# EFR32_Port_Pins.net
KiCad netlist of a schematic drawn in Altium Designer
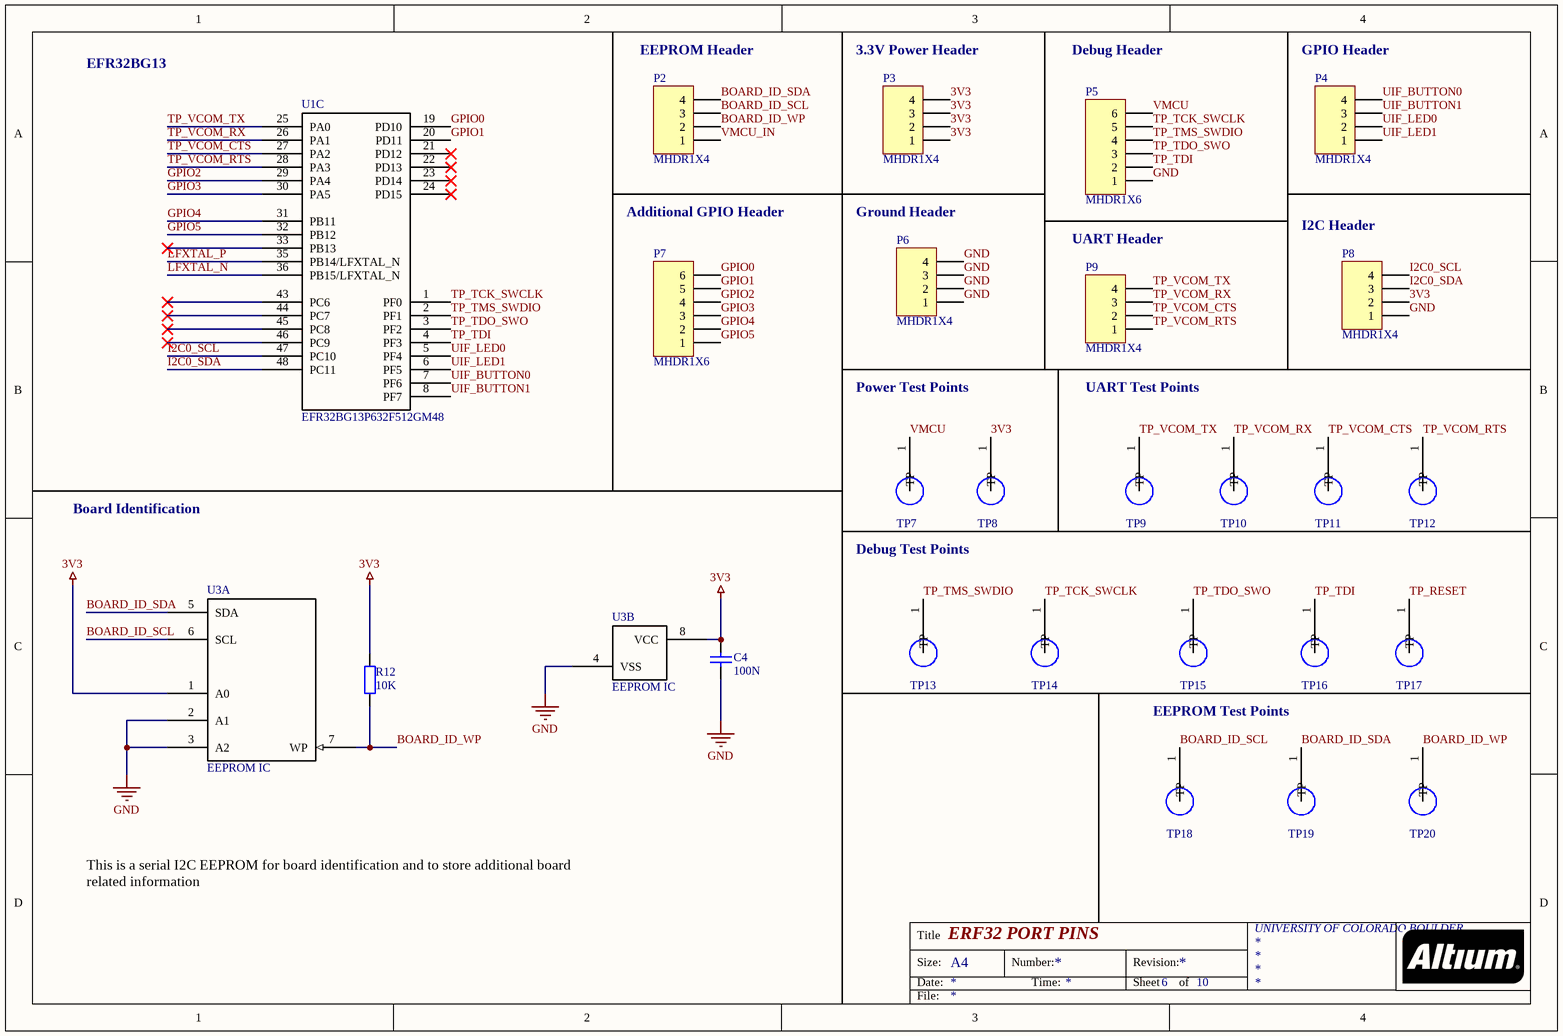
[diagram p0: EFR32_Port_Pins.SchDoc]

(export (version "E")
  (design (tool "Eeschema 10.0.6"))
  (components
    (comp (ref "C4")
      (value "100N")
      (footprint "1608[0603]")
      (description "CAP CER 0.1UF 16V X7R 0603")
      (fields
        (field (name "DIGI-KEY PART NUMBER") "1276-1005-1-ND")
        (field (name "MANUFACTURER") "Samsung Electro-Mechanics")
      )
      (libsource (lib "Miscellaneous Devices") (part "Cap"))
    )
    (comp (ref "P2")
      (value "MHDR1X4")
      (footprint "MHDR1X4")
      (description "CONN HEADER VERT 4POS 2.54MM")
      (fields
        (field (name "DIGI-KEY PART NUMBER") "732-5317-ND")
        (field (name "MANUFACTURER") "Würth Elektronik")
      )
      (libsource (lib "Miscellaneous Connectors") (part "MHDR1X4"))
    )
    (comp (ref "P3")
      (value "MHDR1X4")
      (footprint "MHDR1X4")
      (description "CONN HEADER VERT 4POS 2.54MM")
      (fields
        (field (name "DIGI-KEY PART NUMBER") "732-5317-ND")
        (field (name "MANUFACTURER") "Würth Elektronik")
      )
      (libsource (lib "Miscellaneous Connectors") (part "MHDR1X4"))
    )
    (comp (ref "P4")
      (value "MHDR1X4")
      (footprint "MHDR1X4")
      (description "CONN HEADER VERT 4POS 2.54MM")
      (fields
        (field (name "DIGI-KEY PART NUMBER") "732-5317-ND")
        (field (name "MANUFACTURER") "Würth Elektronik")
      )
      (libsource (lib "Miscellaneous Connectors") (part "MHDR1X4"))
    )
    (comp (ref "P5")
      (value "MHDR1X6")
      (footprint "MHDR1X6")
      (description "CONN HEADER VERT 6POS 2.54MM")
      (fields
        (field (name "DIGI-KEY PART NUMBER") "609-3263-ND")
        (field (name "MANUFACTURER") "Amphenol ICC (FCI)")
      )
      (libsource (lib "Miscellaneous Connectors") (part "MHDR1X6"))
    )
    (comp (ref "P6")
      (value "MHDR1X4")
      (footprint "MHDR1X4")
      (description "CONN HEADER VERT 4POS 2.54MM")
      (fields
        (field (name "DIGI-KEY PART NUMBER") "732-5317-ND")
        (field (name "MANUFACTURER") "Würth Elektronik")
      )
      (libsource (lib "Miscellaneous Connectors") (part "MHDR1X4"))
    )
    (comp (ref "P7")
      (value "MHDR1X6")
      (footprint "MHDR1X6")
      (description "CONN HEADER VERT 6POS 2.54MM")
      (fields
        (field (name "DIGI-KEY PART NUMBER") "609-3263-ND")
        (field (name "MANUFACTURER") "Amphenol ICC (FCI)")
      )
      (libsource (lib "Miscellaneous Connectors") (part "MHDR1X6"))
    )
    (comp (ref "P8")
      (value "MHDR1X4")
      (footprint "MHDR1X4")
      (description "CONN HEADER VERT 4POS 2.54MM")
      (fields
        (field (name "DIGI-KEY PART NUMBER") "732-5317-ND")
        (field (name "MANUFACTURER") "Würth Elektronik")
      )
      (libsource (lib "Miscellaneous Connectors") (part "MHDR1X4"))
    )
    (comp (ref "P9")
      (value "MHDR1X4")
      (footprint "MHDR1X4")
      (description "CONN HEADER VERT 4POS 2.54MM")
      (fields
        (field (name "DIGI-KEY PART NUMBER") "732-5317-ND")
        (field (name "MANUFACTURER") "Würth Elektronik")
      )
      (libsource (lib "Miscellaneous Connectors") (part "MHDR1X4"))
    )
    (comp (ref "R12")
      (value "10K")
      (footprint "AXIAL-0.4")
      (description "RES 10K OHM 1% 1/8W 0603")
      (fields
        (field (name "DIGI-KEY PART NUMBER") "RNCP0603FTD10K0CT-ND")
        (field (name "MANUFACTURER") "Stackpole Electronics Inc")
      )
      (libsource (lib "Miscellaneous Devices") (part "Res2"))
    )
    (comp (ref "TP7")
      (value "TP")
      (footprint "*TP380X203")
      (description "PC TEST POINT MINIATURE")
      (fields
        (field (name "MANUFACTURER") "Keystone Electronics")
        (field (name "DIGI-KEY PART NUMBER") "36-5019CT-ND")
      )
      (libsource (lib "TP") (part "TP"))
    )
    (comp (ref "TP8")
      (value "TP")
      (footprint "*TP380X203")
      (description "PC TEST POINT MINIATURE")
      (fields
        (field (name "MANUFACTURER") "Keystone Electronics")
        (field (name "DIGI-KEY PART NUMBER") "36-5019CT-ND")
      )
      (libsource (lib "TP") (part "TP"))
    )
    (comp (ref "TP9")
      (value "TP")
      (footprint "*TP380X203")
      (description "PC TEST POINT MINIATURE")
      (fields
        (field (name "MANUFACTURER") "Keystone Electronics")
        (field (name "DIGI-KEY PART NUMBER") "36-5019CT-ND")
      )
      (libsource (lib "TP") (part "TP"))
    )
    (comp (ref "TP10")
      (value "TP")
      (footprint "*TP380X203")
      (description "PC TEST POINT MINIATURE")
      (fields
        (field (name "MANUFACTURER") "Keystone Electronics")
        (field (name "DIGI-KEY PART NUMBER") "36-5019CT-ND")
      )
      (libsource (lib "TP") (part "TP"))
    )
    (comp (ref "TP11")
      (value "TP")
      (footprint "*TP380X203")
      (description "PC TEST POINT MINIATURE")
      (fields
        (field (name "MANUFACTURER") "Keystone Electronics")
        (field (name "DIGI-KEY PART NUMBER") "36-5019CT-ND")
      )
      (libsource (lib "TP") (part "TP"))
    )
    (comp (ref "TP12")
      (value "TP")
      (footprint "*TP380X203")
      (description "PC TEST POINT MINIATURE")
      (fields
        (field (name "MANUFACTURER") "Keystone Electronics")
        (field (name "DIGI-KEY PART NUMBER") "36-5019CT-ND")
      )
      (libsource (lib "TP") (part "TP"))
    )
    (comp (ref "TP13")
      (value "TP")
      (footprint "*TP380X203")
      (description "PC TEST POINT MINIATURE")
      (fields
        (field (name "MANUFACTURER") "Keystone Electronics")
        (field (name "DIGI-KEY PART NUMBER") "36-5019CT-ND")
      )
      (libsource (lib "TP") (part "TP"))
    )
    (comp (ref "TP14")
      (value "TP")
      (footprint "*TP380X203")
      (description "PC TEST POINT MINIATURE")
      (fields
        (field (name "MANUFACTURER") "Keystone Electronics")
        (field (name "DIGI-KEY PART NUMBER") "36-5019CT-ND")
      )
      (libsource (lib "TP") (part "TP"))
    )
    (comp (ref "TP15")
      (value "TP")
      (footprint "*TP380X203")
      (description "PC TEST POINT MINIATURE")
      (fields
        (field (name "MANUFACTURER") "Keystone Electronics")
        (field (name "DIGI-KEY PART NUMBER") "36-5019CT-ND")
      )
      (libsource (lib "TP") (part "TP"))
    )
    (comp (ref "TP16")
      (value "TP")
      (footprint "*TP380X203")
      (description "PC TEST POINT MINIATURE")
      (fields
        (field (name "MANUFACTURER") "Keystone Electronics")
        (field (name "DIGI-KEY PART NUMBER") "36-5019CT-ND")
      )
      (libsource (lib "TP") (part "TP"))
    )
    (comp (ref "TP17")
      (value "TP")
      (footprint "*TP380X203")
      (description "PC TEST POINT MINIATURE")
      (fields
        (field (name "MANUFACTURER") "Keystone Electronics")
        (field (name "DIGI-KEY PART NUMBER") "36-5019CT-ND")
      )
      (libsource (lib "TP") (part "TP"))
    )
    (comp (ref "TP18")
      (value "TP")
      (footprint "*TP380X203")
      (description "PC TEST POINT MINIATURE")
      (fields
        (field (name "MANUFACTURER") "Keystone Electronics")
        (field (name "DIGI-KEY PART NUMBER") "36-5019CT-ND")
      )
      (libsource (lib "TP") (part "TP"))
    )
    (comp (ref "TP19")
      (value "TP")
      (footprint "*TP380X203")
      (description "PC TEST POINT MINIATURE")
      (fields
        (field (name "MANUFACTURER") "Keystone Electronics")
        (field (name "DIGI-KEY PART NUMBER") "36-5019CT-ND")
      )
      (libsource (lib "TP") (part "TP"))
    )
    (comp (ref "TP20")
      (value "TP")
      (footprint "*TP380X203")
      (description "PC TEST POINT MINIATURE")
      (fields
        (field (name "MANUFACTURER") "Keystone Electronics")
        (field (name "DIGI-KEY PART NUMBER") "36-5019CT-ND")
      )
      (libsource (lib "TP") (part "TP"))
    )
    (comp (ref "U1")
      (value "EFR32BG13P632F512GM48")
      (footprint "*QFN50P700X700X90-49N")
      (description "MCU")
      (fields
        (field (name "MANUFACTURER") "Silicon Labs")
        (field (name "MANUFACTURER PART NUMBER") "EFR32BG13P632F512GM48-BR")
      )
      (libsource (lib "EFR32BG13") (part "EFR32BG13"))
    )
    (comp (ref "U3")
      (value "EEPROM IC")
      (footprint "*SON50P200X300X80-8N")
      (description "EEPROM 2K 256X8 SER EE 1.8V 18 I/O 10-BIT ADC")
      (fields
        (field (name "MOUSER PART NUMBER") "579-24AA024T-I/MNY")
        (field (name "MANUFACTURER PART NUMBER") "24AA024T-I/MNY")
      )
      (libsource (lib "EEPROM_IC") (part "EEPROM IC"))
    )
  )
  (nets
    (net (code "1") (name "/BOARD_ID_SCL") (class "Default")
      (node (ref "P2") (pin "3") (pinfunction "3_3") (pintype "passive"))
      (node (ref "TP18") (pin "1") (pinfunction "TP_1") (pintype "passive"))
      (node (ref "U3") (pin "6") (pinfunction "SCL_6") (pintype "passive"))
    )
    (net (code "2") (name "/BOARD_ID_SDA") (class "Default")
      (node (ref "P2") (pin "4") (pinfunction "4_4") (pintype "passive"))
      (node (ref "TP19") (pin "1") (pinfunction "TP_1") (pintype "passive"))
      (node (ref "U3") (pin "5") (pinfunction "SDA_5") (pintype "passive"))
    )
    (net (code "3") (name "/BOARD_ID_WP") (class "Default")
      (node (ref "P2") (pin "2") (pinfunction "2_2") (pintype "passive"))
      (node (ref "R12") (pin "1") (pinfunction "1_1") (pintype "passive"))
      (node (ref "TP20") (pin "1") (pinfunction "TP_1") (pintype "passive"))
      (node (ref "U3") (pin "7") (pinfunction "WP_7") (pintype "input"))
    )
    (net (code "4") (name "/GPIO0") (class "Default")
      (node (ref "P7") (pin "6") (pinfunction "6_6") (pintype "passive"))
      (node (ref "U1") (pin "19") (pinfunction "PD10_19") (pintype "passive"))
    )
    (net (code "5") (name "/GPIO1") (class "Default")
      (node (ref "P7") (pin "5") (pinfunction "5_5") (pintype "passive"))
      (node (ref "U1") (pin "20") (pinfunction "PD11_20") (pintype "passive"))
    )
    (net (code "6") (name "/GPIO2") (class "Default")
      (node (ref "P7") (pin "4") (pinfunction "4_4") (pintype "passive"))
      (node (ref "U1") (pin "29") (pinfunction "PA4_29") (pintype "passive"))
    )
    (net (code "7") (name "/GPIO3") (class "Default")
      (node (ref "P7") (pin "3") (pinfunction "3_3") (pintype "passive"))
      (node (ref "U1") (pin "30") (pinfunction "PA5_30") (pintype "passive"))
    )
    (net (code "8") (name "/GPIO4") (class "Default")
      (node (ref "P7") (pin "2") (pinfunction "2_2") (pintype "passive"))
      (node (ref "U1") (pin "31") (pinfunction "PB11_31") (pintype "passive"))
    )
    (net (code "9") (name "/GPIO5") (class "Default")
      (node (ref "P7") (pin "1") (pinfunction "1_1") (pintype "passive"))
      (node (ref "U1") (pin "32") (pinfunction "PB12_32") (pintype "passive"))
    )
    (net (code "10") (name "/I2C0_SCL") (class "Default")
      (node (ref "P8") (pin "4") (pinfunction "4_4") (pintype "passive"))
      (node (ref "U1") (pin "47") (pinfunction "PC10_47") (pintype "passive"))
    )
    (net (code "11") (name "/I2C0_SDA") (class "Default")
      (node (ref "P8") (pin "3") (pinfunction "3_3") (pintype "passive"))
      (node (ref "U1") (pin "48") (pinfunction "PC11_48") (pintype "passive"))
    )
    (net (code "12") (name "/LFXTAL_N") (class "Default")
      (node (ref "U1") (pin "36") (pinfunction "PB15/LFXTAL_N_36") (pintype "passive"))
    )
    (net (code "13") (name "/LFXTAL_P") (class "Default")
      (node (ref "U1") (pin "35") (pinfunction "PB14/LFXTAL_N_35") (pintype "passive"))
    )
    (net (code "14") (name "/TP_RESET") (class "Default")
      (node (ref "TP17") (pin "1") (pinfunction "TP_1") (pintype "passive"))
    )
    (net (code "15") (name "/TP_TCK_SWCLK") (class "Default")
      (node (ref "P5") (pin "5") (pinfunction "5_5") (pintype "passive"))
      (node (ref "TP14") (pin "1") (pinfunction "TP_1") (pintype "passive"))
      (node (ref "U1") (pin "1") (pinfunction "PF0_1") (pintype "passive"))
    )
    (net (code "16") (name "/TP_TDI") (class "Default")
      (node (ref "P5") (pin "2") (pinfunction "2_2") (pintype "passive"))
      (node (ref "TP16") (pin "1") (pinfunction "TP_1") (pintype "passive"))
      (node (ref "U1") (pin "4") (pinfunction "PF3_4") (pintype "passive"))
    )
    (net (code "17") (name "/TP_TDO_SWO") (class "Default")
      (node (ref "P5") (pin "3") (pinfunction "3_3") (pintype "passive"))
      (node (ref "TP15") (pin "1") (pinfunction "TP_1") (pintype "passive"))
      (node (ref "U1") (pin "3") (pinfunction "PF2_3") (pintype "passive"))
    )
    (net (code "18") (name "/TP_TMS_SWDIO") (class "Default")
      (node (ref "P5") (pin "4") (pinfunction "4_4") (pintype "passive"))
      (node (ref "TP13") (pin "1") (pinfunction "TP_1") (pintype "passive"))
      (node (ref "U1") (pin "2") (pinfunction "PF1_2") (pintype "passive"))
    )
    (net (code "19") (name "/TP_VCOM_CTS") (class "Default")
      (node (ref "P9") (pin "2") (pinfunction "2_2") (pintype "passive"))
      (node (ref "TP11") (pin "1") (pinfunction "TP_1") (pintype "passive"))
      (node (ref "U1") (pin "27") (pinfunction "PA2_27") (pintype "passive"))
    )
    (net (code "20") (name "/TP_VCOM_RTS") (class "Default")
      (node (ref "P9") (pin "1") (pinfunction "1_1") (pintype "passive"))
      (node (ref "TP12") (pin "1") (pinfunction "TP_1") (pintype "passive"))
      (node (ref "U1") (pin "28") (pinfunction "PA3_28") (pintype "passive"))
    )
    (net (code "21") (name "/TP_VCOM_RX") (class "Default")
      (node (ref "P9") (pin "3") (pinfunction "3_3") (pintype "passive"))
      (node (ref "TP10") (pin "1") (pinfunction "TP_1") (pintype "passive"))
      (node (ref "U1") (pin "26") (pinfunction "PA1_26") (pintype "passive"))
    )
    (net (code "22") (name "/TP_VCOM_TX") (class "Default")
      (node (ref "P9") (pin "4") (pinfunction "4_4") (pintype "passive"))
      (node (ref "TP9") (pin "1") (pinfunction "TP_1") (pintype "passive"))
      (node (ref "U1") (pin "25") (pinfunction "PA0_25") (pintype "passive"))
    )
    (net (code "23") (name "/UIF_BUTTON0") (class "Default")
      (node (ref "P4") (pin "4") (pinfunction "4_4") (pintype "passive"))
      (node (ref "U1") (pin "7") (pinfunction "PF6_7") (pintype "passive"))
    )
    (net (code "24") (name "/UIF_BUTTON1") (class "Default")
      (node (ref "P4") (pin "3") (pinfunction "3_3") (pintype "passive"))
      (node (ref "U1") (pin "8") (pinfunction "PF7_8") (pintype "passive"))
    )
    (net (code "25") (name "/UIF_LED0") (class "Default")
      (node (ref "P4") (pin "2") (pinfunction "2_2") (pintype "passive"))
      (node (ref "U1") (pin "5") (pinfunction "PF4_5") (pintype "passive"))
    )
    (net (code "26") (name "/UIF_LED1") (class "Default")
      (node (ref "P4") (pin "1") (pinfunction "1_1") (pintype "passive"))
      (node (ref "U1") (pin "6") (pinfunction "PF5_6") (pintype "passive"))
    )
    (net (code "27") (name "/VMCU") (class "Default")
      (node (ref "P5") (pin "6") (pinfunction "6_6") (pintype "passive"))
      (node (ref "TP7") (pin "1") (pinfunction "TP_1") (pintype "passive"))
    )
    (net (code "28") (name "/VMCU_IN") (class "Default")
      (node (ref "P2") (pin "1") (pinfunction "1_1") (pintype "passive"))
    )
    (net (code "29") (name "3V3") (class "Default")
      (node (ref "C4") (pin "2") (pinfunction "2_2") (pintype "passive"))
      (node (ref "P3") (pin "1") (pinfunction "1_1") (pintype "passive"))
      (node (ref "P3") (pin "2") (pinfunction "2_2") (pintype "passive"))
      (node (ref "P3") (pin "3") (pinfunction "3_3") (pintype "passive"))
      (node (ref "P3") (pin "4") (pinfunction "4_4") (pintype "passive"))
      (node (ref "P8") (pin "2") (pinfunction "2_2") (pintype "passive"))
      (node (ref "R12") (pin "2") (pinfunction "2_2") (pintype "passive"))
      (node (ref "TP8") (pin "1") (pinfunction "TP_1") (pintype "passive"))
      (node (ref "U3") (pin "1") (pinfunction "A0_1") (pintype "passive"))
      (node (ref "U3") (pin "8") (pinfunction "VCC_8") (pintype "passive"))
    )
    (net (code "30") (name "GND") (class "Default")
      (node (ref "C4") (pin "1") (pinfunction "1_1") (pintype "passive"))
      (node (ref "P5") (pin "1") (pinfunction "1_1") (pintype "passive"))
      (node (ref "P6") (pin "1") (pinfunction "1_1") (pintype "passive"))
      (node (ref "P6") (pin "2") (pinfunction "2_2") (pintype "passive"))
      (node (ref "P6") (pin "3") (pinfunction "3_3") (pintype "passive"))
      (node (ref "P6") (pin "4") (pinfunction "4_4") (pintype "passive"))
      (node (ref "P8") (pin "1") (pinfunction "1_1") (pintype "passive"))
      (node (ref "U3") (pin "2") (pinfunction "A1_2") (pintype "passive"))
      (node (ref "U3") (pin "3") (pinfunction "A2_3") (pintype "passive"))
      (node (ref "U3") (pin "4") (pinfunction "VSS_4") (pintype "passive"))
    )
    (net (code "31") (name "unconnected-(U1C-PB13-Pad33)") (class "Default")
      (node (ref "U1") (pin "33") (pinfunction "PB13_33") (pintype "passive+no_connect"))
    )
    (net (code "32") (name "unconnected-(U1C-PC6-Pad43)") (class "Default")
      (node (ref "U1") (pin "43") (pinfunction "PC6_43") (pintype "passive+no_connect"))
    )
    (net (code "33") (name "unconnected-(U1C-PC7-Pad44)") (class "Default")
      (node (ref "U1") (pin "44") (pinfunction "PC7_44") (pintype "passive+no_connect"))
    )
    (net (code "34") (name "unconnected-(U1C-PC8-Pad45)") (class "Default")
      (node (ref "U1") (pin "45") (pinfunction "PC8_45") (pintype "passive+no_connect"))
    )
    (net (code "35") (name "unconnected-(U1C-PC9-Pad46)") (class "Default")
      (node (ref "U1") (pin "46") (pinfunction "PC9_46") (pintype "passive+no_connect"))
    )
    (net (code "36") (name "unconnected-(U1C-PD12-Pad21)") (class "Default")
      (node (ref "U1") (pin "21") (pinfunction "PD12_21") (pintype "passive+no_connect"))
    )
    (net (code "37") (name "unconnected-(U1C-PD13-Pad22)") (class "Default")
      (node (ref "U1") (pin "22") (pinfunction "PD13_22") (pintype "passive+no_connect"))
    )
    (net (code "38") (name "unconnected-(U1C-PD14-Pad23)") (class "Default")
      (node (ref "U1") (pin "23") (pinfunction "PD14_23") (pintype "passive+no_connect"))
    )
    (net (code "39") (name "unconnected-(U1C-PD15-Pad24)") (class "Default")
      (node (ref "U1") (pin "24") (pinfunction "PD15_24") (pintype "passive+no_connect"))
    )
  )
)
